# Arduino_Sersor_Board.net
KiCad netlist of a schematic drawn in EAGLE
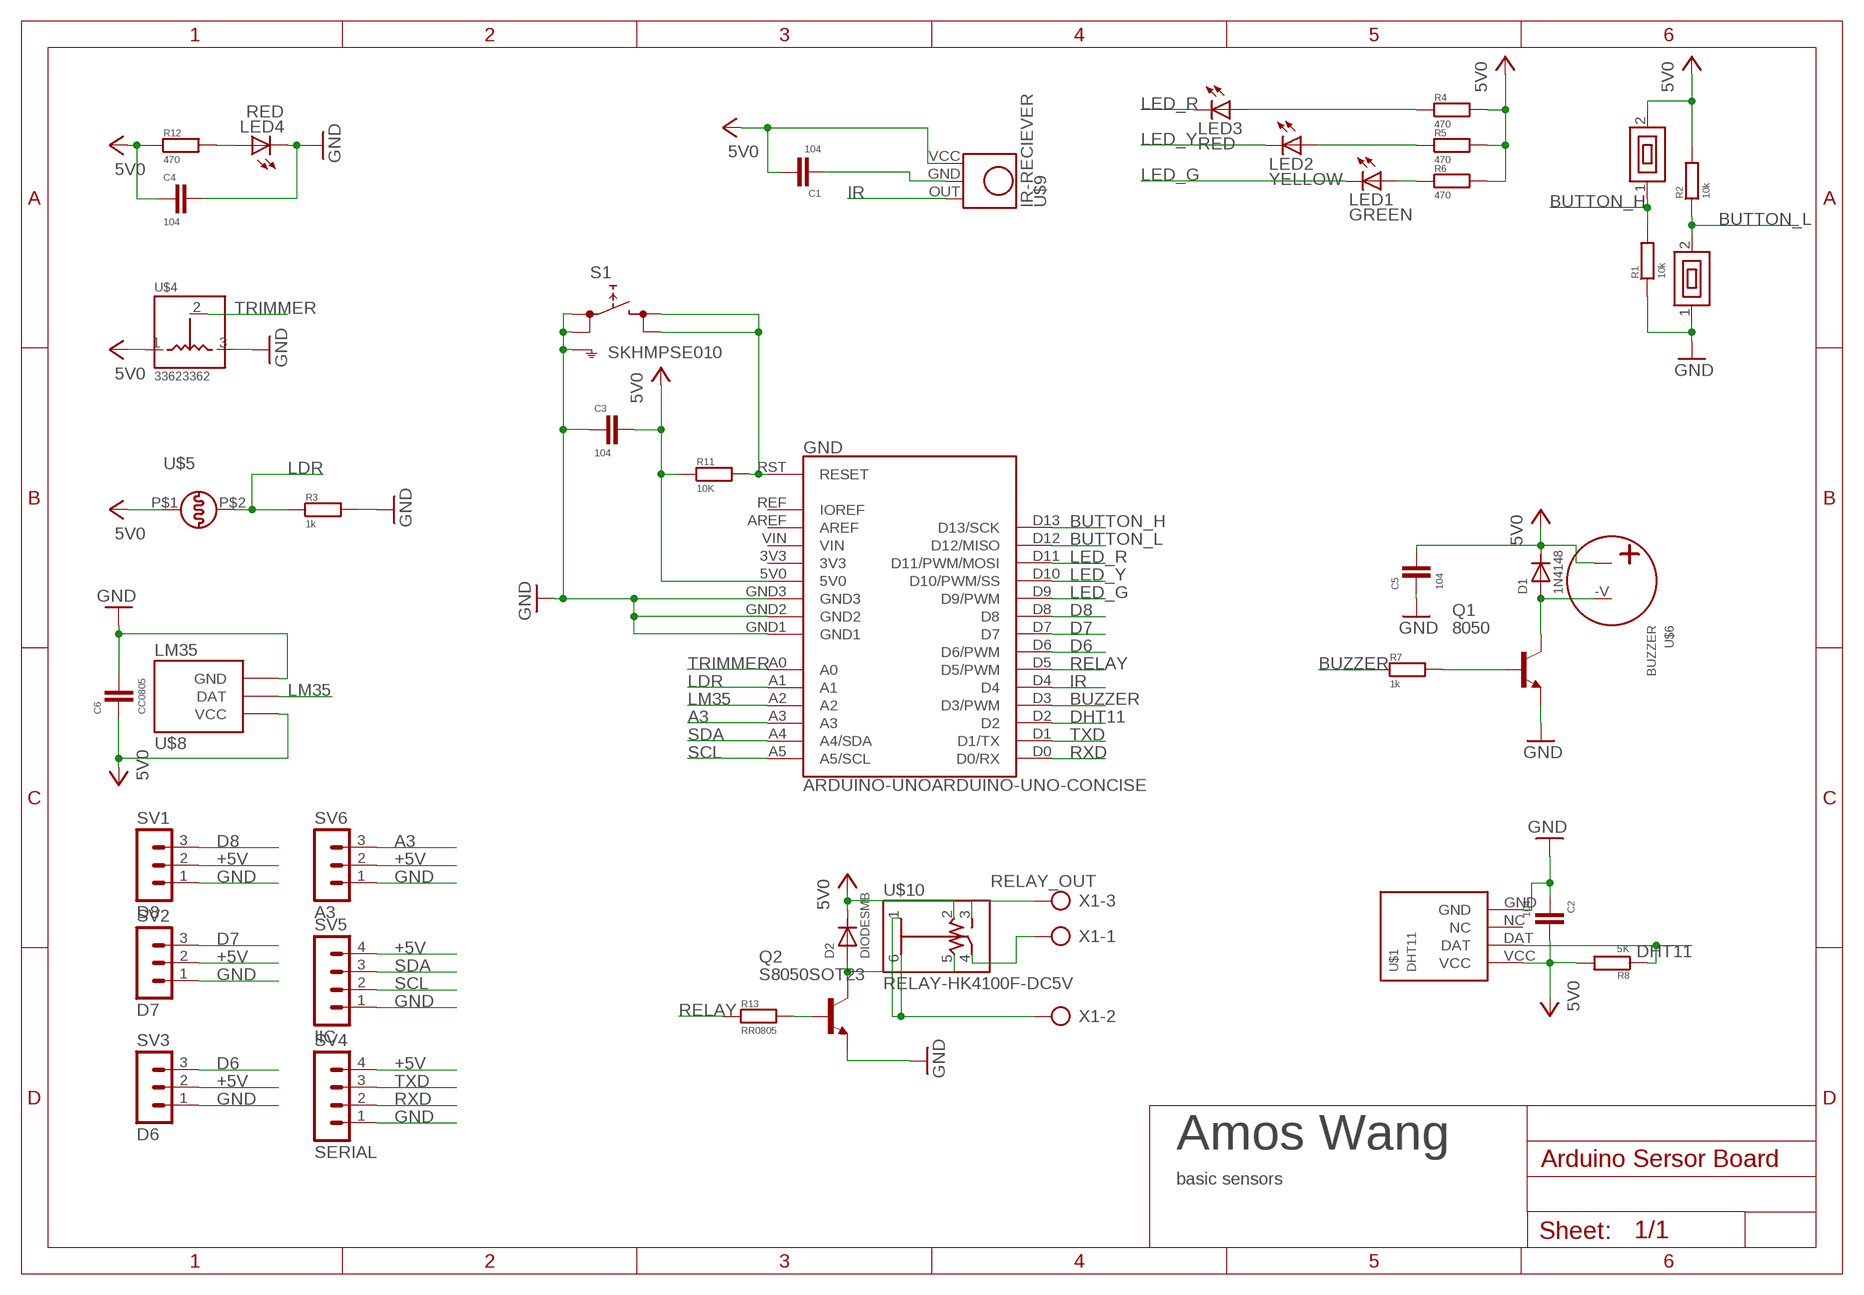
[diagram p0: schematic, sheet 1]

(export (version "E")
  (design (tool "Eeschema 10.0.6"))
  (components
    (comp (ref "C1")
      (value "104")
      (footprint "eagle-import:C0805")
      (libsource (lib "eagle-import") (part "CC0805"))
    )
    (comp (ref "C2")
      (value "104")
      (footprint "eagle-import:C0805")
      (libsource (lib "eagle-import") (part "CC0805"))
    )
    (comp (ref "C3")
      (value "104")
      (footprint "eagle-import:C0805")
      (libsource (lib "eagle-import") (part "CC0805"))
    )
    (comp (ref "C4")
      (value "104")
      (footprint "eagle-import:C0805")
      (libsource (lib "eagle-import") (part "CC0805"))
    )
    (comp (ref "C5")
      (value "104")
      (footprint "eagle-import:C0805")
      (libsource (lib "eagle-import") (part "CC0805"))
    )
    (comp (ref "C6")
      (value "CC0805")
      (footprint "eagle-import:C0805")
      (libsource (lib "eagle-import") (part "CC0805"))
    )
    (comp (ref "D1")
      (value "1N4148")
      (footprint "eagle-import:SMB")
      (libsource (lib "eagle-import") (part "DIODESMB"))
    )
    (comp (ref "D2")
      (value "DIODESMB")
      (footprint "eagle-import:SMB")
      (libsource (lib "eagle-import") (part "DIODESMB"))
    )
    (comp (ref "GND")
      (value "ARDUINO-UNOARDUINO-UNO-CONCISE")
      (footprint "eagle-import:ARDUINO-UNO")
      (libsource (lib "eagle-import") (part "ARDUINO-UNOARDUINO-UNO-CONCISE"))
    )
    (comp (ref "LED1")
      (value "GREEN")
      (footprint "eagle-import:LED2X5")
      (libsource (lib "eagle-import") (part "LEDSQR2X5"))
    )
    (comp (ref "LED2")
      (value "YELLOW")
      (footprint "eagle-import:LED2X5")
      (libsource (lib "eagle-import") (part "LEDSQR2X5"))
    )
    (comp (ref "LED3")
      (value "RED")
      (footprint "eagle-import:LED2X5")
      (libsource (lib "eagle-import") (part "LEDSQR2X5"))
    )
    (comp (ref "LED4")
      (value "RED")
      (footprint "eagle-import:CHIP-LED0805")
      (libsource (lib "eagle-import") (part "LEDCHIP-LED0805"))
    )
    (comp (ref "Q1")
      (value "8050")
      (footprint "eagle-import:SOT23")
      (libsource (lib "eagle-import") (part "S8050SOT23"))
    )
    (comp (ref "Q2")
      (value "S8050SOT23")
      (footprint "eagle-import:SOT23")
      (libsource (lib "eagle-import") (part "S8050SOT23"))
    )
    (comp (ref "R1")
      (value "10k")
      (footprint "eagle-import:R0805")
      (libsource (lib "eagle-import") (part "RR0805"))
    )
    (comp (ref "R2")
      (value "10k")
      (footprint "eagle-import:R0805")
      (libsource (lib "eagle-import") (part "RR0805"))
    )
    (comp (ref "R3")
      (value "1k")
      (footprint "eagle-import:R0805")
      (libsource (lib "eagle-import") (part "RR0805"))
    )
    (comp (ref "R4")
      (value "470")
      (footprint "eagle-import:R0805")
      (libsource (lib "eagle-import") (part "RR0805"))
    )
    (comp (ref "R5")
      (value "470")
      (footprint "eagle-import:R0805")
      (libsource (lib "eagle-import") (part "RR0805"))
    )
    (comp (ref "R6")
      (value "470")
      (footprint "eagle-import:R0805")
      (libsource (lib "eagle-import") (part "RR0805"))
    )
    (comp (ref "R7")
      (value "1k")
      (footprint "eagle-import:R0805")
      (libsource (lib "eagle-import") (part "RR0805"))
    )
    (comp (ref "R8")
      (value "5K")
      (footprint "eagle-import:R0805")
      (libsource (lib "eagle-import") (part "RR0805"))
    )
    (comp (ref "R11")
      (value "10K")
      (footprint "eagle-import:R0805")
      (libsource (lib "eagle-import") (part "RR0805"))
    )
    (comp (ref "R12")
      (value "470")
      (footprint "eagle-import:R0805")
      (libsource (lib "eagle-import") (part "RR0805"))
    )
    (comp (ref "R13")
      (value "RR0805")
      (footprint "eagle-import:R0805")
      (libsource (lib "eagle-import") (part "RR0805"))
    )
    (comp (ref "S1")
      (value "SKHMPSE010")
      (footprint "eagle-import:SKHMPXE010")
      (libsource (lib "eagle-import") (part "SKHMPE010S"))
    )
    (comp (ref "SV1")
      (value "D8")
      (footprint "eagle-import:MA03-1")
      (libsource (lib "eagle-import") (part "MA03-1"))
    )
    (comp (ref "SV2")
      (value "D7")
      (footprint "eagle-import:MA03-1")
      (libsource (lib "eagle-import") (part "MA03-1"))
    )
    (comp (ref "SV3")
      (value "D6")
      (footprint "eagle-import:MA03-1")
      (libsource (lib "eagle-import") (part "MA03-1"))
    )
    (comp (ref "SV4")
      (value "SERIAL")
      (footprint "eagle-import:MA04-1")
      (libsource (lib "eagle-import") (part "MA04-1"))
    )
    (comp (ref "SV5")
      (value "IIC")
      (footprint "eagle-import:MA04-1")
      (libsource (lib "eagle-import") (part "MA04-1"))
    )
    (comp (ref "SV6")
      (value "A3")
      (footprint "eagle-import:MA03-1")
      (libsource (lib "eagle-import") (part "MA03-1"))
    )
    (comp (ref "U$1")
      (value "DHT11")
      (footprint "eagle-import:DHT11")
      (libsource (lib "eagle-import") (part "DHT11"))
    )
    (comp (ref "U$2")
      (value "SMD-36SMD-3*6")
      (footprint "eagle-import:SMD-3_6")
      (libsource (lib "eagle-import") (part "SMD-36SMD-36"))
    )
    (comp (ref "U$3")
      (value "SMD-36SMD-3*6")
      (footprint "eagle-import:SMD-3_6")
      (libsource (lib "eagle-import") (part "SMD-36SMD-36"))
    )
    (comp (ref "U$4")
      (value "33623362")
      (footprint "eagle-import:3362")
      (libsource (lib "eagle-import") (part "33623362"))
    )
    (comp (ref "U$5")
      (value "LDR")
      (footprint "eagle-import:LDR")
      (libsource (lib "eagle-import") (part "LDR"))
    )
    (comp (ref "U$6")
      (value "BUZZER")
      (footprint "eagle-import:BUZZER")
      (libsource (lib "eagle-import") (part "BUZZER"))
    )
    (comp (ref "U$8")
      (value "LM35")
      (footprint "eagle-import:TO92")
      (libsource (lib "eagle-import") (part "LM35"))
    )
    (comp (ref "U$9")
      (value "IR-RECIEVER")
      (footprint "eagle-import:IR-RECIEVER")
      (libsource (lib "eagle-import") (part "IR-RECIEVER"))
    )
    (comp (ref "U$10")
      (value "RELAY-HK4100F-DC5V")
      (footprint "eagle-import:RELAY-HK4100F-DC5V")
      (libsource (lib "eagle-import") (part "RELAY-HK4100F-DC5V"))
    )
    (comp (ref "X1")
      (value "RELAY_OUT")
      (footprint "eagle-import:AK500_3")
      (libsource (lib "eagle-import") (part "AK500/3"))
    )
  )
  (nets
    (net (code "1") (name "/A3") (class "Default")
      (node (ref "GND") (pin "A3") (pinfunction "A3_A3") (pintype "bidirectional"))
      (node (ref "SV6") (pin "3") (pinfunction "3_3") (pintype "passive"))
    )
    (net (code "2") (name "/BUTTON_H") (class "Default")
      (node (ref "GND") (pin "D13") (pinfunction "D13/SCK_D13") (pintype "bidirectional"))
      (node (ref "R1") (pin "2") (pinfunction "2_2") (pintype "bidirectional"))
      (node (ref "U$2") (pin "1") (pinfunction "1_1") (pintype "bidirectional"))
    )
    (net (code "3") (name "/BUTTON_L") (class "Default")
      (node (ref "GND") (pin "D12") (pinfunction "D12/MISO_D12") (pintype "bidirectional"))
      (node (ref "R2") (pin "1") (pinfunction "1_1") (pintype "bidirectional"))
      (node (ref "U$3") (pin "2") (pinfunction "2_2") (pintype "bidirectional"))
    )
    (net (code "4") (name "/BUZZER") (class "Default")
      (node (ref "GND") (pin "D3") (pinfunction "D3/PWM_D3") (pintype "bidirectional"))
      (node (ref "R7") (pin "1") (pinfunction "1_1") (pintype "bidirectional"))
    )
    (net (code "5") (name "/D6") (class "Default")
      (node (ref "GND") (pin "D6") (pinfunction "D6/PWM_D6") (pintype "bidirectional"))
      (node (ref "SV3") (pin "3") (pinfunction "3_3") (pintype "passive"))
    )
    (net (code "6") (name "/D7") (class "Default")
      (node (ref "GND") (pin "D7") (pinfunction "D7_D7") (pintype "bidirectional"))
      (node (ref "SV2") (pin "3") (pinfunction "3_3") (pintype "passive"))
    )
    (net (code "7") (name "/D8") (class "Default")
      (node (ref "GND") (pin "D8") (pinfunction "D8_D8") (pintype "bidirectional"))
      (node (ref "SV1") (pin "3") (pinfunction "3_3") (pintype "passive"))
    )
    (net (code "8") (name "/DHT11") (class "Default")
      (node (ref "GND") (pin "D2") (pinfunction "D2_D2") (pintype "bidirectional"))
      (node (ref "R8") (pin "1") (pinfunction "1_1") (pintype "bidirectional"))
      (node (ref "U$1") (pin "DAT") (pinfunction "DAT_DAT") (pintype "bidirectional"))
    )
    (net (code "9") (name "/IR") (class "Default")
      (node (ref "GND") (pin "D4") (pinfunction "D4_D4") (pintype "bidirectional"))
      (node (ref "U$9") (pin "OUT") (pinfunction "OUT_OUT") (pintype "bidirectional"))
    )
    (net (code "10") (name "/LDR") (class "Default")
      (node (ref "GND") (pin "A1") (pinfunction "A1_A1") (pintype "bidirectional"))
      (node (ref "R3") (pin "1") (pinfunction "1_1") (pintype "bidirectional"))
      (node (ref "U$5") (pin "P$2") (pinfunction "P$2_P$2") (pintype "bidirectional"))
    )
    (net (code "11") (name "/LED_G") (class "Default")
      (node (ref "GND") (pin "D9") (pinfunction "D9/PWM_D9") (pintype "bidirectional"))
      (node (ref "LED1") (pin "K") (pinfunction "C_K") (pintype "passive"))
    )
    (net (code "12") (name "/LED_R") (class "Default")
      (node (ref "GND") (pin "D11") (pinfunction "D11/PWM/MOSI_D11") (pintype "bidirectional"))
      (node (ref "LED3") (pin "K") (pinfunction "C_K") (pintype "passive"))
    )
    (net (code "13") (name "/LED_Y") (class "Default")
      (node (ref "GND") (pin "D10") (pinfunction "D10/PWM/SS_D10") (pintype "bidirectional"))
      (node (ref "LED2") (pin "K") (pinfunction "C_K") (pintype "passive"))
    )
    (net (code "14") (name "/LM35") (class "Default")
      (node (ref "GND") (pin "A2") (pinfunction "A2_A2") (pintype "bidirectional"))
      (node (ref "U$8") (pin "2") (pinfunction "DAT_2") (pintype "bidirectional"))
    )
    (net (code "15") (name "/RELAY") (class "Default")
      (node (ref "GND") (pin "D5") (pinfunction "D5/PWM_D5") (pintype "bidirectional"))
      (node (ref "R13") (pin "1") (pinfunction "1_1") (pintype "bidirectional"))
    )
    (net (code "16") (name "/RXD") (class "Default")
      (node (ref "GND") (pin "D0") (pinfunction "D0/RX_D0") (pintype "bidirectional"))
      (node (ref "SV4") (pin "2") (pinfunction "2_2") (pintype "passive"))
    )
    (net (code "17") (name "/SCL") (class "Default")
      (node (ref "GND") (pin "A5") (pinfunction "A5/SCL_A5") (pintype "bidirectional"))
      (node (ref "SV5") (pin "2") (pinfunction "2_2") (pintype "passive"))
    )
    (net (code "18") (name "/SDA") (class "Default")
      (node (ref "GND") (pin "A4") (pinfunction "A4/SDA_A4") (pintype "bidirectional"))
      (node (ref "SV5") (pin "3") (pinfunction "3_3") (pintype "passive"))
    )
    (net (code "19") (name "/TRIMMER") (class "Default")
      (node (ref "GND") (pin "A0") (pinfunction "A0_A0") (pintype "bidirectional"))
      (node (ref "U$4") (pin "2") (pinfunction "2_2") (pintype "bidirectional"))
    )
    (net (code "20") (name "/TXD") (class "Default")
      (node (ref "GND") (pin "D1") (pinfunction "D1/TX_D1") (pintype "bidirectional"))
      (node (ref "SV4") (pin "3") (pinfunction "3_3") (pintype "passive"))
    )
    (net (code "21") (name "5V0") (class "Default")
      (node (ref "C1") (pin "1") (pinfunction "1_1") (pintype "bidirectional"))
      (node (ref "C2") (pin "1") (pinfunction "1_1") (pintype "bidirectional"))
      (node (ref "C3") (pin "1") (pinfunction "1_1") (pintype "bidirectional"))
      (node (ref "C4") (pin "2") (pinfunction "2_2") (pintype "bidirectional"))
      (node (ref "C5") (pin "1") (pinfunction "1_1") (pintype "bidirectional"))
      (node (ref "C6") (pin "2") (pinfunction "2_2") (pintype "bidirectional"))
      (node (ref "D1") (pin "1") (pinfunction "1_1") (pintype "bidirectional"))
      (node (ref "D2") (pin "1") (pinfunction "1_1") (pintype "bidirectional"))
      (node (ref "GND") (pin "5V0") (pinfunction "5V0_5V0") (pintype "bidirectional"))
      (node (ref "R11") (pin "1") (pinfunction "1_1") (pintype "bidirectional"))
      (node (ref "R12") (pin "1") (pinfunction "1_1") (pintype "bidirectional"))
      (node (ref "R2") (pin "2") (pinfunction "2_2") (pintype "bidirectional"))
      (node (ref "R4") (pin "2") (pinfunction "2_2") (pintype "bidirectional"))
      (node (ref "R5") (pin "2") (pinfunction "2_2") (pintype "bidirectional"))
      (node (ref "R6") (pin "2") (pinfunction "2_2") (pintype "bidirectional"))
      (node (ref "R8") (pin "2") (pinfunction "2_2") (pintype "bidirectional"))
      (node (ref "SV1") (pin "2") (pinfunction "2_2") (pintype "passive"))
      (node (ref "SV2") (pin "2") (pinfunction "2_2") (pintype "passive"))
      (node (ref "SV3") (pin "2") (pinfunction "2_2") (pintype "passive"))
      (node (ref "SV4") (pin "4") (pinfunction "4_4") (pintype "passive"))
      (node (ref "SV5") (pin "4") (pinfunction "4_4") (pintype "passive"))
      (node (ref "SV6") (pin "2") (pinfunction "2_2") (pintype "passive"))
      (node (ref "U$1") (pin "VCC") (pinfunction "VCC_VCC") (pintype "bidirectional"))
      (node (ref "U$10") (pin "2") (pinfunction "2_2") (pintype "bidirectional"))
      (node (ref "U$2") (pin "2") (pinfunction "2_2") (pintype "bidirectional"))
      (node (ref "U$4") (pin "1") (pinfunction "1_1") (pintype "bidirectional"))
      (node (ref "U$5") (pin "P$1") (pinfunction "P$1_P$1") (pintype "bidirectional"))
      (node (ref "U$6") (pin "+V") (pinfunction "+V_+V") (pintype "bidirectional"))
      (node (ref "U$8") (pin "1") (pinfunction "VCC_1") (pintype "bidirectional"))
      (node (ref "U$9") (pin "VCC") (pinfunction "VCC_VCC") (pintype "bidirectional"))
    )
    (net (code "22") (name "GND") (class "Default")
      (node (ref "C2") (pin "2") (pinfunction "2_2") (pintype "bidirectional"))
      (node (ref "C3") (pin "2") (pinfunction "2_2") (pintype "bidirectional"))
      (node (ref "C4") (pin "1") (pinfunction "1_1") (pintype "bidirectional"))
      (node (ref "C5") (pin "2") (pinfunction "2_2") (pintype "bidirectional"))
      (node (ref "C6") (pin "1") (pinfunction "1_1") (pintype "bidirectional"))
      (node (ref "GND") (pin "GND1") (pinfunction "GND1_GND1") (pintype "bidirectional"))
      (node (ref "GND") (pin "GND2") (pinfunction "GND2_GND2") (pintype "bidirectional"))
      (node (ref "GND") (pin "GND3") (pinfunction "GND3_GND3") (pintype "bidirectional"))
      (node (ref "LED4") (pin "C") (pinfunction "C_C") (pintype "passive"))
      (node (ref "Q1") (pin "E") (pinfunction "E_E") (pintype "passive"))
      (node (ref "Q2") (pin "E") (pinfunction "E_E") (pintype "passive"))
      (node (ref "R1") (pin "1") (pinfunction "1_1") (pintype "bidirectional"))
      (node (ref "R3") (pin "2") (pinfunction "2_2") (pintype "bidirectional"))
      (node (ref "S1") (pin "1") (pinfunction "1.1_1") (pintype "passive"))
      (node (ref "S1") (pin "2") (pinfunction "1.2_2") (pintype "passive"))
      (node (ref "S1") (pin "5") (pinfunction "SH_5") (pintype "passive"))
      (node (ref "SV1") (pin "1") (pinfunction "1_1") (pintype "passive"))
      (node (ref "SV2") (pin "1") (pinfunction "1_1") (pintype "passive"))
      (node (ref "SV3") (pin "1") (pinfunction "1_1") (pintype "passive"))
      (node (ref "SV4") (pin "1") (pinfunction "1_1") (pintype "passive"))
      (node (ref "SV5") (pin "1") (pinfunction "1_1") (pintype "passive"))
      (node (ref "SV6") (pin "1") (pinfunction "1_1") (pintype "passive"))
      (node (ref "U$1") (pin "GND") (pinfunction "GND_GND") (pintype "bidirectional"))
      (node (ref "U$3") (pin "1") (pinfunction "1_1") (pintype "bidirectional"))
      (node (ref "U$4") (pin "3") (pinfunction "3_3") (pintype "bidirectional"))
      (node (ref "U$8") (pin "3") (pinfunction "GND_3") (pintype "bidirectional"))
    )
    (net (code "23") (name "Net-(C1-Pad2)") (class "Default")
      (node (ref "C1") (pin "2") (pinfunction "2_2") (pintype "bidirectional"))
      (node (ref "U$9") (pin "GND") (pinfunction "GND_GND") (pintype "bidirectional"))
    )
    (net (code "24") (name "Net-(D1-Pad2)") (class "Default")
      (node (ref "D1") (pin "2") (pinfunction "2_2") (pintype "bidirectional"))
      (node (ref "Q1") (pin "C") (pinfunction "C_C") (pintype "passive"))
      (node (ref "U$6") (pin "-V") (pinfunction "-V_-V") (pintype "bidirectional"))
    )
    (net (code "25") (name "Net-(D2-Pad2)") (class "Default")
      (node (ref "D2") (pin "2") (pinfunction "2_2") (pintype "bidirectional"))
      (node (ref "Q2") (pin "C") (pinfunction "C_C") (pintype "passive"))
      (node (ref "U$10") (pin "5") (pinfunction "5_5") (pintype "bidirectional"))
    )
    (net (code "26") (name "Net-(GND-RESET)") (class "Default")
      (node (ref "GND") (pin "RST") (pinfunction "RESET_RST") (pintype "bidirectional"))
      (node (ref "R11") (pin "2") (pinfunction "2_2") (pintype "bidirectional"))
      (node (ref "S1") (pin "3") (pinfunction "2.1_3") (pintype "passive"))
      (node (ref "S1") (pin "4") (pinfunction "2.2_4") (pintype "passive"))
    )
    (net (code "27") (name "Net-(LED1-PadA)") (class "Default")
      (node (ref "LED1") (pin "A") (pinfunction "A_A") (pintype "passive"))
      (node (ref "R6") (pin "1") (pinfunction "1_1") (pintype "bidirectional"))
    )
    (net (code "28") (name "Net-(LED2-PadA)") (class "Default")
      (node (ref "LED2") (pin "A") (pinfunction "A_A") (pintype "passive"))
      (node (ref "R5") (pin "1") (pinfunction "1_1") (pintype "bidirectional"))
    )
    (net (code "29") (name "Net-(LED3-PadA)") (class "Default")
      (node (ref "LED3") (pin "A") (pinfunction "A_A") (pintype "passive"))
      (node (ref "R4") (pin "1") (pinfunction "1_1") (pintype "bidirectional"))
    )
    (net (code "30") (name "Net-(LED4-PadA)") (class "Default")
      (node (ref "LED4") (pin "A") (pinfunction "A_A") (pintype "passive"))
      (node (ref "R12") (pin "2") (pinfunction "2_2") (pintype "bidirectional"))
    )
    (net (code "31") (name "Net-(Q1-PadB)") (class "Default")
      (node (ref "Q1") (pin "B") (pinfunction "B_B") (pintype "passive"))
      (node (ref "R7") (pin "2") (pinfunction "2_2") (pintype "bidirectional"))
    )
    (net (code "32") (name "Net-(Q2-PadB)") (class "Default")
      (node (ref "Q2") (pin "B") (pinfunction "B_B") (pintype "passive"))
      (node (ref "R13") (pin "2") (pinfunction "2_2") (pintype "bidirectional"))
    )
    (net (code "33") (name "Net-(X1A-KL)") (class "Default")
      (node (ref "U$10") (pin "4") (pinfunction "4_4") (pintype "bidirectional"))
      (node (ref "X1") (pin "1") (pinfunction "KL_1") (pintype "passive"))
    )
    (net (code "34") (name "Net-(X1B-KL)") (class "Default")
      (node (ref "U$10") (pin "1") (pinfunction "1_1") (pintype "bidirectional"))
      (node (ref "U$10") (pin "6") (pinfunction "6_6") (pintype "bidirectional"))
      (node (ref "X1") (pin "2") (pinfunction "KL_2") (pintype "passive"))
    )
    (net (code "35") (name "Net-(X1C-KL)") (class "Default")
      (node (ref "U$10") (pin "3") (pinfunction "3_3") (pintype "bidirectional"))
      (node (ref "X1") (pin "3") (pinfunction "KL_3") (pintype "passive"))
    )
    (net (code "36") (name "unconnected-(GND-IOREF-PadREF)") (class "Default")
      (node (ref "GND") (pin "REF") (pinfunction "IOREF_REF") (pintype "bidirectional"))
    )
    (net (code "37") (name "unconnected-(GND-Pad3V3)") (class "Default")
      (node (ref "GND") (pin "3V3") (pinfunction "3V3_3V3") (pintype "bidirectional"))
    )
    (net (code "38") (name "unconnected-(GND-PadAREF)") (class "Default")
      (node (ref "GND") (pin "AREF") (pinfunction "AREF_AREF") (pintype "bidirectional"))
    )
    (net (code "39") (name "unconnected-(GND-PadVIN)") (class "Default")
      (node (ref "GND") (pin "VIN") (pinfunction "VIN_VIN") (pintype "bidirectional"))
    )
    (net (code "40") (name "unconnected-(U$1-PadNC)") (class "Default")
      (node (ref "U$1") (pin "NC") (pinfunction "NC_NC") (pintype "bidirectional"))
    )
  )
)
